# PIC32MK.net
KiCad netlist of a schematic drawn in Altium Designer
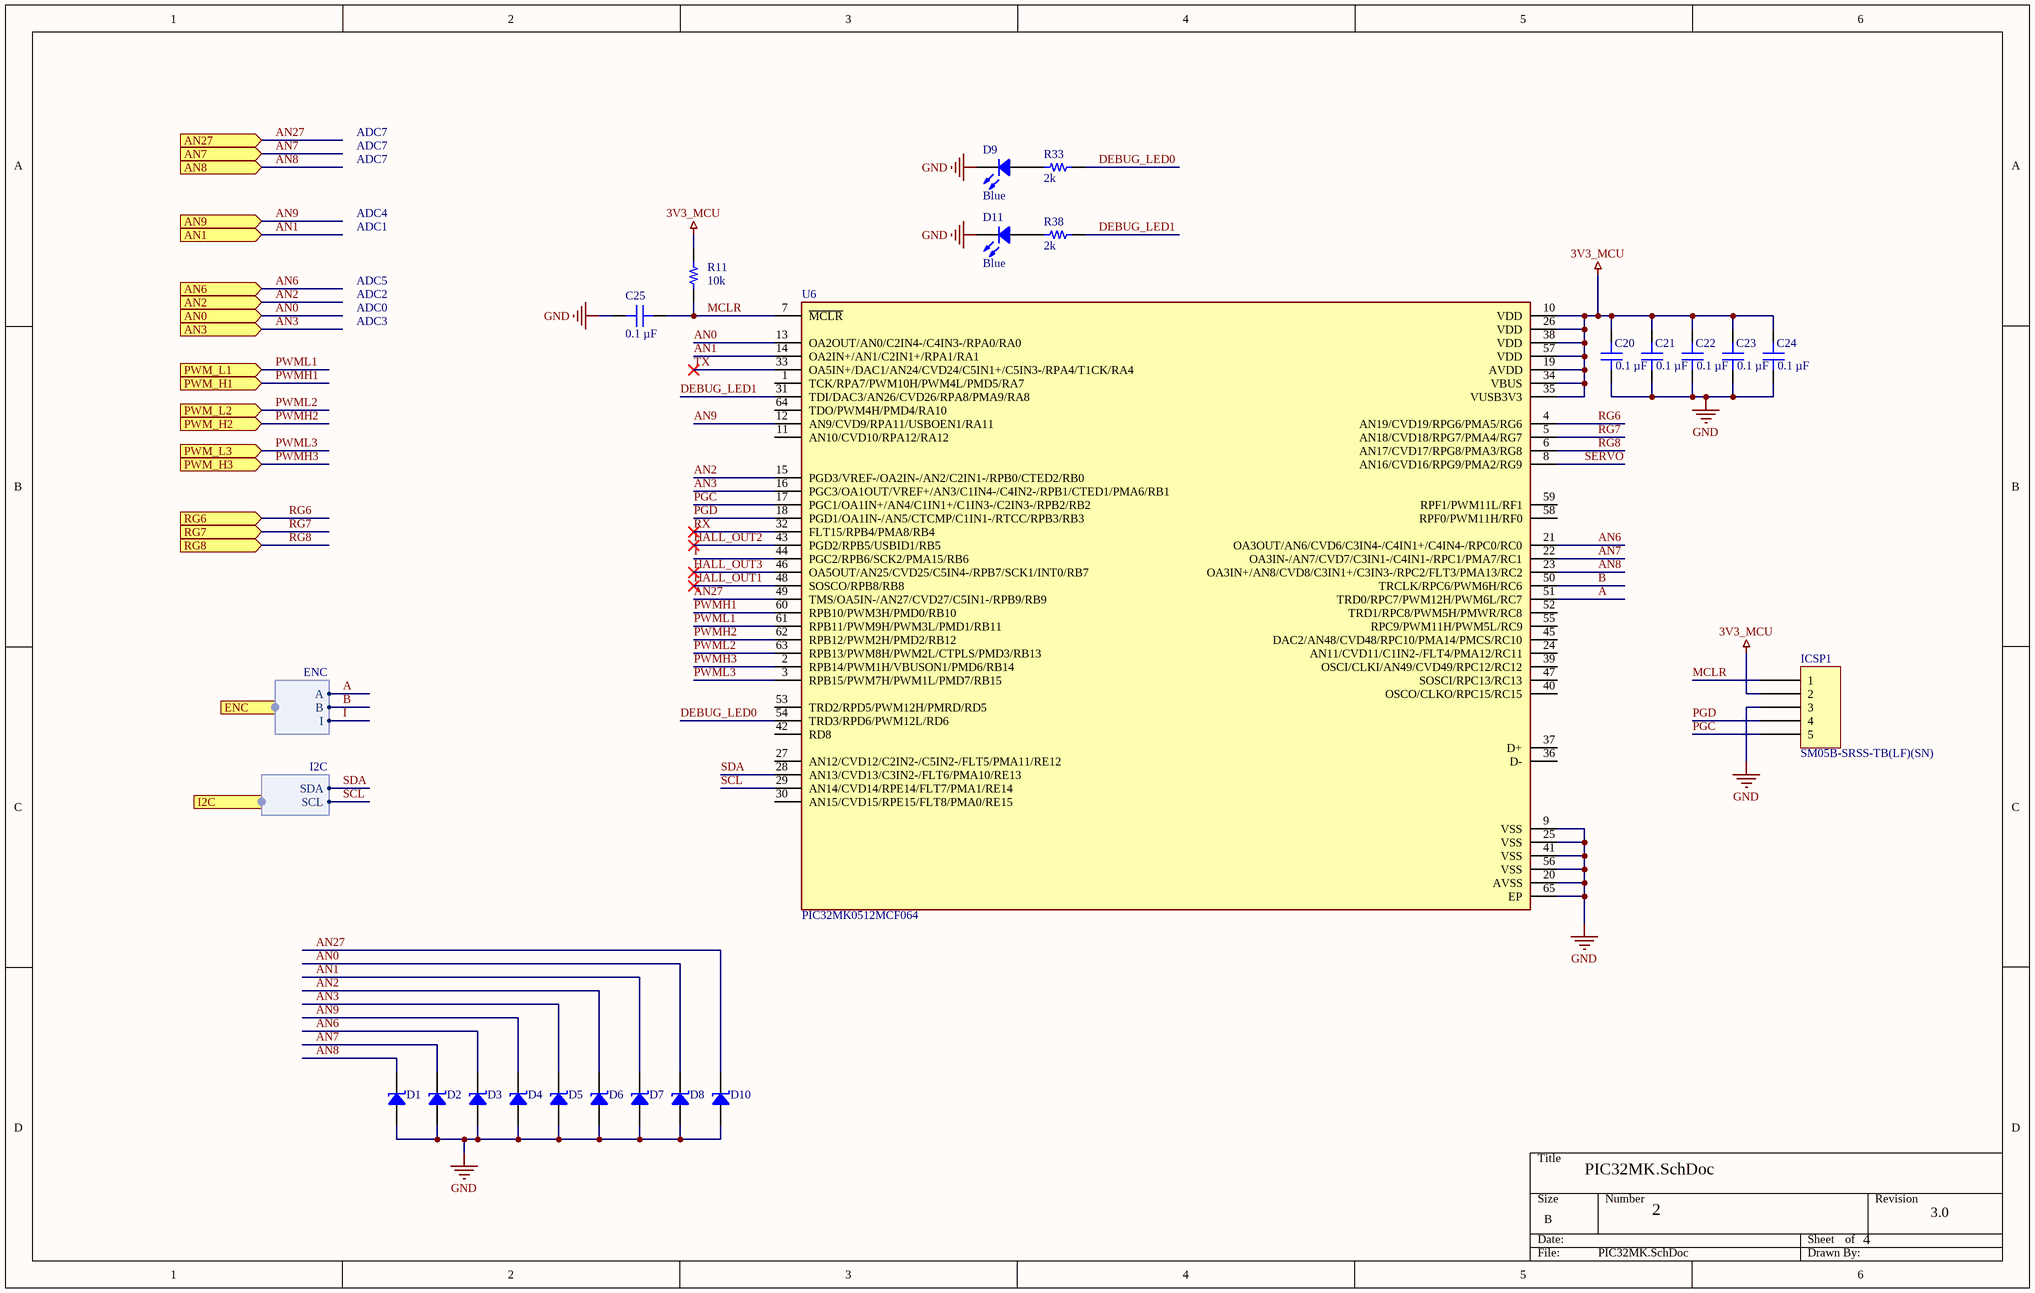
[diagram p0: PIC32MK.SchDoc]

(export (version "E")
  (design (tool "Eeschema 10.0.6"))
  (components
    (comp (ref "C20")
      (value "0.1 µF")
      (footprint "CAP 0402_1005")
      (description "CAP CER 0.1UF 16V X7R 0402")
      (fields (field (name "PART NUMBER") "C0402C104K4RACAUTO") (field (name "MANUFACTURER") "KEMET"))
      (libsource (lib "Celestial Altium Library - altium_library") (part "Capacitor"))
    )
    (comp (ref "C21")
      (value "0.1 µF")
      (footprint "CAP 0402_1005")
      (description "CAP CER 0.1UF 16V X7R 0402")
      (fields (field (name "PART NUMBER") "C0402C104K4RACAUTO") (field (name "MANUFACTURER") "KEMET"))
      (libsource (lib "Celestial Altium Library - altium_library") (part "Capacitor"))
    )
    (comp (ref "C22")
      (value "0.1 µF")
      (footprint "CAP 0402_1005")
      (description "CAP CER 0.1UF 16V X7R 0402")
      (fields (field (name "PART NUMBER") "C0402C104K4RACAUTO") (field (name "MANUFACTURER") "KEMET"))
      (libsource (lib "Celestial Altium Library - altium_library") (part "Capacitor"))
    )
    (comp (ref "C23")
      (value "0.1 µF")
      (footprint "CAP 0402_1005")
      (description "CAP CER 0.1UF 16V X7R 0402")
      (fields (field (name "PART NUMBER") "C0402C104K4RACAUTO") (field (name "MANUFACTURER") "KEMET"))
      (libsource (lib "Celestial Altium Library - altium_library") (part "Capacitor"))
    )
    (comp (ref "C24")
      (value "0.1 µF")
      (footprint "CAP 0402_1005")
      (description "CAP CER 0.1UF 16V X7R 0402")
      (fields (field (name "PART NUMBER") "C0402C104K4RACAUTO") (field (name "MANUFACTURER") "KEMET"))
      (libsource (lib "Celestial Altium Library - altium_library") (part "Capacitor"))
    )
    (comp (ref "C25")
      (value "0.1 µF")
      (footprint "CAP 0402_1005")
      (description "CAP CER 0.1UF 16V X7R 0402")
      (fields (field (name "PART NUMBER") "C0402C104K4RACAUTO") (field (name "MANUFACTURER") "KEMET"))
      (libsource (lib "Celestial Altium Library - altium_library") (part "Capacitor"))
    )
    (comp (ref "D1")
      (value "ESDLC3V3L-TP")
      (footprint "0402")
      (description "TVS DIODE 3.3V 15V DFN1006-2")
      (fields (field (name "MANUFACTURER") "Micro Commercial Co"))
      (libsource (lib "Celestial Altium Library - altium_library") (part "DIODE TVS UNI"))
    )
    (comp (ref "D2")
      (value "ESDLC3V3L-TP")
      (footprint "0402")
      (description "TVS DIODE 3.3V 15V DFN1006-2")
      (fields (field (name "MANUFACTURER") "Micro Commercial Co"))
      (libsource (lib "Celestial Altium Library - altium_library") (part "DIODE TVS UNI"))
    )
    (comp (ref "D3")
      (value "ESDLC3V3L-TP")
      (footprint "0402")
      (description "TVS DIODE 3.3V 15V DFN1006-2")
      (fields (field (name "MANUFACTURER") "Micro Commercial Co"))
      (libsource (lib "Celestial Altium Library - altium_library") (part "DIODE TVS UNI"))
    )
    (comp (ref "D4")
      (value "ESDLC3V3L-TP")
      (footprint "0402")
      (description "TVS DIODE 3.3V 15V DFN1006-2")
      (fields (field (name "MANUFACTURER") "Micro Commercial Co"))
      (libsource (lib "Celestial Altium Library - altium_library") (part "DIODE TVS UNI"))
    )
    (comp (ref "D5")
      (value "ESDLC3V3L-TP")
      (footprint "0402")
      (description "TVS DIODE 3.3V 15V DFN1006-2")
      (fields (field (name "MANUFACTURER") "Micro Commercial Co"))
      (libsource (lib "Celestial Altium Library - altium_library") (part "DIODE TVS UNI"))
    )
    (comp (ref "D6")
      (value "ESDLC3V3L-TP")
      (footprint "0402")
      (description "TVS DIODE 3.3V 15V DFN1006-2")
      (fields (field (name "MANUFACTURER") "Micro Commercial Co"))
      (libsource (lib "Celestial Altium Library - altium_library") (part "DIODE TVS UNI"))
    )
    (comp (ref "D7")
      (value "ESDLC3V3L-TP")
      (footprint "0402")
      (description "TVS DIODE 3.3V 15V DFN1006-2")
      (fields (field (name "MANUFACTURER") "Micro Commercial Co"))
      (libsource (lib "Celestial Altium Library - altium_library") (part "DIODE TVS UNI"))
    )
    (comp (ref "D8")
      (value "ESDLC3V3L-TP")
      (footprint "0402")
      (description "TVS DIODE 3.3V 15V DFN1006-2")
      (fields (field (name "MANUFACTURER") "Micro Commercial Co"))
      (libsource (lib "Celestial Altium Library - altium_library") (part "DIODE TVS UNI"))
    )
    (comp (ref "D9")
      (value "Blue")
      (footprint "LED 0603_1608 GREEN")
      (description "Blue LED")
      (fields (field (name "PART NUMBER") "XZCDGK53W-8VF") (field (name "MANUFACTURER") "SunLED"))
      (libsource (lib "Celestial Altium Library - altium_library") (part "LED"))
    )
    (comp (ref "D10")
      (value "ESDLC3V3L-TP")
      (footprint "0402")
      (description "TVS DIODE 3.3V 15V DFN1006-2")
      (fields (field (name "MANUFACTURER") "Micro Commercial Co"))
      (libsource (lib "Celestial Altium Library - altium_library") (part "DIODE TVS UNI"))
    )
    (comp (ref "D11")
      (value "Blue")
      (footprint "LED 0603_1608 GREEN")
      (description "Blue LED")
      (fields (field (name "PART NUMBER") "XZCDGK53W-8VF") (field (name "MANUFACTURER") "SunLED"))
      (libsource (lib "Celestial Altium Library - altium_library") (part "LED"))
    )
    (comp (ref "ICSP1")
      (value "SM05B-SRSS-TB(LF)(SN)")
      (footprint "JST SM05B-SRSS-TB")
      (description "CONN HEADER SMD R/A 5POS 1MM")
      (fields (field (name "MANUFACTURER") "JST Sales America Inc."))
      (libsource (lib "Celestial Altium Library - altium_library") (part "5 Pin"))
    )
    (comp (ref "R11")
      (value "10k")
      (footprint "RES 0402_1005")
      (description "RES 14.3K OHM 1% 1/10W 0402")
      (fields
        (field (name "PART NUMBER") "RK73H1ETTP1432F")
        (field (name "MANUFACTURER") "KOA Speer Electronics, Inc.")
      )
      (libsource (lib "Celestial Altium Library - altium_library") (part "Resistor"))
    )
    (comp (ref "R33")
      (value "2k")
      (footprint "RES 0402_1005")
      (description "RES 14.3K OHM 1% 1/10W 0402")
      (fields
        (field (name "PART NUMBER") "RK73H1ETTP1432F")
        (field (name "MANUFACTURER") "KOA Speer Electronics, Inc.")
      )
      (libsource (lib "Celestial Altium Library - altium_library") (part "Resistor"))
    )
    (comp (ref "R38")
      (value "2k")
      (footprint "RES 0402_1005")
      (description "RES 14.3K OHM 1% 1/10W 0402")
      (fields
        (field (name "PART NUMBER") "RK73H1ETTP1432F")
        (field (name "MANUFACTURER") "KOA Speer Electronics, Inc.")
      )
      (libsource (lib "Celestial Altium Library - altium_library") (part "Resistor"))
    )
    (comp (ref "U6")
      (value "PIC32MK0512MCF064")
      (footprint "QFN50P900X900X100-65N")
      (description "PIC32MK Microcontroller IC 32-Bit 120MHz 1MB _1M x 8_ FLASH 64-TQFP _10x10_")
      (fields
        (field (name "MP") "PIC32MK1024MCF064-I/PT")
        (field (name "DIGI-KEY_PART_NUMBER") "PIC32MK1024MCF064-I/PT-ND")
      )
      (libsource (lib "IC") (part "PIC32MK0512MCF064"))
    )
  )
  (nets
    (net (code "3") (name "/A") (class "Default")
      (node (ref "U6") (pin "51") (pinfunction "TRD0/RPC7/PWM12H/PWM6L/RC7_51") (pintype "passive"))
    )
    (net (code "4") (name "/AN0") (class "Default")
      (node (ref "D8") (pin "2") (pinfunction "2_2") (pintype "passive"))
      (node (ref "U6") (pin "13") (pinfunction "OA2OUT/AN0/C2IN4-/C4IN3-/RPA0/RA0_13") (pintype "passive"))
    )
    (net (code "5") (name "/AN1") (class "Default")
      (node (ref "D7") (pin "2") (pinfunction "2_2") (pintype "passive"))
      (node (ref "U6") (pin "14") (pinfunction "OA2IN+/AN1/C2IN1+/RPA1/RA1_14") (pintype "passive"))
    )
    (net (code "6") (name "/AN2") (class "Default")
      (node (ref "D6") (pin "2") (pinfunction "2_2") (pintype "passive"))
      (node (ref "U6") (pin "15") (pinfunction "PGD3/VREF-/OA2IN-/AN2/C2IN1-/RPB0/CTED2/RB0_15") (pintype "passive"))
    )
    (net (code "7") (name "/AN3") (class "Default")
      (node (ref "D5") (pin "2") (pinfunction "2_2") (pintype "passive"))
      (node (ref "U6") (pin "16") (pinfunction "PGC3/OA1OUT/VREF+/AN3/C1IN4-/C4IN2-/RPB1/CTED1/PMA6/RB1_16") (pintype "passive"))
    )
    (net (code "8") (name "/AN6") (class "Default")
      (node (ref "D3") (pin "2") (pinfunction "2_2") (pintype "passive"))
      (node (ref "U6") (pin "21") (pinfunction "OA3OUT/AN6/CVD6/C3IN4-/C4IN1+/C4IN4-/RPC0/RC0_21") (pintype "passive"))
    )
    (net (code "9") (name "/AN7") (class "Default")
      (node (ref "D2") (pin "2") (pinfunction "2_2") (pintype "passive"))
      (node (ref "U6") (pin "22") (pinfunction "OA3IN-/AN7/CVD7/C3IN1-/C4IN1-/RPC1/PMA7/RC1_22") (pintype "passive"))
    )
    (net (code "10") (name "/AN8") (class "Default")
      (node (ref "D1") (pin "2") (pinfunction "2_2") (pintype "passive"))
      (node (ref "U6") (pin "23") (pinfunction "OA3IN+/AN8/CVD8/C3IN1+/C3IN3-/RPC2/FLT3/PMA13/RC2_23") (pintype "passive"))
    )
    (net (code "11") (name "/AN9") (class "Default")
      (node (ref "D4") (pin "2") (pinfunction "2_2") (pintype "passive"))
      (node (ref "U6") (pin "12") (pinfunction "AN9/CVD9/RPA11/USBOEN1/RA11_12") (pintype "passive"))
    )
    (net (code "12") (name "/AN27") (class "Default")
      (node (ref "D10") (pin "2") (pinfunction "2_2") (pintype "passive"))
      (node (ref "U6") (pin "49") (pinfunction "TMS/OA5IN-/AN27/CVD27/C5IN1-/RPB9/RB9_49") (pintype "passive"))
    )
    (net (code "13") (name "/B") (class "Default")
      (node (ref "U6") (pin "50") (pinfunction "TRCLK/RPC6/PWM6H/RC6_50") (pintype "passive"))
    )
    (net (code "14") (name "/DEBUG_LED0") (class "Default")
      (node (ref "R33") (pin "1") (pinfunction "1_1") (pintype "passive"))
      (node (ref "U6") (pin "54") (pinfunction "TRD3/RPD6/PWM12L/RD6_54") (pintype "passive"))
    )
    (net (code "15") (name "/DEBUG_LED1") (class "Default")
      (node (ref "R38") (pin "1") (pinfunction "1_1") (pintype "passive"))
      (node (ref "U6") (pin "31") (pinfunction "TDI/DAC3/AN26/CVD26/RPA8/PMA9/RA8_31") (pintype "passive"))
    )
    (net (code "16") (name "/HALL_OUT1") (class "Default")
      (node (ref "U6") (pin "48") (pinfunction "SOSCO/RPB8/RB8_48") (pintype "passive+no_connect"))
    )
    (net (code "17") (name "/HALL_OUT2") (class "Default")
      (node (ref "U6") (pin "43") (pinfunction "PGD2/RPB5/USBID1/RB5_43") (pintype "passive+no_connect"))
    )
    (net (code "18") (name "/HALL_OUT3") (class "Default")
      (node (ref "U6") (pin "46") (pinfunction "OA5OUT/AN25/CVD25/C5IN4-/RPB7/SCK1/INT0/RB7_46") (pintype "passive+no_connect"))
    )
    (net (code "19") (name "/I") (class "Default")
      (node (ref "U6") (pin "44") (pinfunction "PGC2/RPB6/SCK2/PMA15/RB6_44") (pintype "passive"))
    )
    (net (code "20") (name "/MCLR") (class "Default")
      (node (ref "C25") (pin "1") (pinfunction "1_1") (pintype "passive"))
      (node (ref "ICSP1") (pin "1") (pinfunction "1_1") (pintype "passive"))
      (node (ref "R11") (pin "1") (pinfunction "1_1") (pintype "passive"))
      (node (ref "U6") (pin "7") (pinfunction "~{MCLR}_7") (pintype "passive"))
    )
    (net (code "21") (name "/PGC") (class "Default")
      (node (ref "ICSP1") (pin "5") (pinfunction "5_5") (pintype "passive"))
      (node (ref "U6") (pin "17") (pinfunction "PGC1/OA1IN+/AN4/C1IN1+/C1IN3-/C2IN3-/RPB2/RB2_17") (pintype "passive"))
    )
    (net (code "22") (name "/PGD") (class "Default")
      (node (ref "ICSP1") (pin "4") (pinfunction "4_4") (pintype "passive"))
      (node (ref "U6") (pin "18") (pinfunction "PGD1/OA1IN-/AN5/CTCMP/C1IN1-/RTCC/RPB3/RB3_18") (pintype "passive"))
    )
    (net (code "23") (name "/PWMH1") (class "Default")
      (node (ref "U6") (pin "60") (pinfunction "RPB10/PWM3H/PMD0/RB10_60") (pintype "passive"))
    )
    (net (code "24") (name "/PWMH2") (class "Default")
      (node (ref "U6") (pin "62") (pinfunction "RPB12/PWM2H/PMD2/RB12_62") (pintype "passive"))
    )
    (net (code "25") (name "/PWMH3") (class "Default")
      (node (ref "U6") (pin "2") (pinfunction "RPB14/PWM1H/VBUSON1/PMD6/RB14_2") (pintype "passive"))
    )
    (net (code "26") (name "/PWML1") (class "Default")
      (node (ref "U6") (pin "61") (pinfunction "RPB11/PWM9H/PWM3L/PMD1/RB11_61") (pintype "passive"))
    )
    (net (code "27") (name "/PWML2") (class "Default")
      (node (ref "U6") (pin "63") (pinfunction "RPB13/PWM8H/PWM2L/CTPLS/PMD3/RB13_63") (pintype "passive"))
    )
    (net (code "28") (name "/PWML3") (class "Default")
      (node (ref "U6") (pin "3") (pinfunction "RPB15/PWM7H/PWM1L/PMD7/RB15_3") (pintype "passive"))
    )
    (net (code "29") (name "/RG6") (class "Default")
      (node (ref "U6") (pin "4") (pinfunction "AN19/CVD19/RPG6/PMA5/RG6_4") (pintype "passive"))
    )
    (net (code "30") (name "/RG7") (class "Default")
      (node (ref "U6") (pin "5") (pinfunction "AN18/CVD18/RPG7/PMA4/RG7_5") (pintype "passive"))
    )
    (net (code "31") (name "/RG8") (class "Default")
      (node (ref "U6") (pin "6") (pinfunction "AN17/CVD17/RPG8/PMA3/RG8_6") (pintype "passive"))
    )
    (net (code "32") (name "/RX") (class "Default")
      (node (ref "U6") (pin "32") (pinfunction "FLT15/RPB4/PMA8/RB4_32") (pintype "passive+no_connect"))
    )
    (net (code "33") (name "/SCL") (class "Default")
      (node (ref "U6") (pin "29") (pinfunction "AN14/CVD14/RPE14/FLT7/PMA1/RE14_29") (pintype "passive"))
    )
    (net (code "34") (name "/SDA") (class "Default")
      (node (ref "U6") (pin "28") (pinfunction "AN13/CVD13/C3IN2-/FLT6/PMA10/RE13_28") (pintype "passive"))
    )
    (net (code "35") (name "/SERVO") (class "Default")
      (node (ref "U6") (pin "8") (pinfunction "AN16/CVD16/RPG9/PMA2/RG9_8") (pintype "passive"))
    )
    (net (code "36") (name "/TX") (class "Default")
      (node (ref "U6") (pin "33") (pinfunction "OA5IN+/DAC1/AN24/CVD24/C5IN1+/C5IN3-/RPA4/T1CK/RA4_33") (pintype "passive+no_connect"))
    )
    (net (code "39") (name "3V3_MCU") (class "Default")
      (node (ref "C20") (pin "2") (pinfunction "2_2") (pintype "passive"))
      (node (ref "C21") (pin "2") (pinfunction "2_2") (pintype "passive"))
      (node (ref "C22") (pin "2") (pinfunction "2_2") (pintype "passive"))
      (node (ref "C23") (pin "2") (pinfunction "2_2") (pintype "passive"))
      (node (ref "C24") (pin "2") (pinfunction "2_2") (pintype "passive"))
      (node (ref "ICSP1") (pin "2") (pinfunction "2_2") (pintype "passive"))
      (node (ref "R11") (pin "2") (pinfunction "2_2") (pintype "passive"))
      (node (ref "U6") (pin "10") (pinfunction "VDD_10") (pintype "power_in"))
      (node (ref "U6") (pin "19") (pinfunction "AVDD_19") (pintype "power_in"))
      (node (ref "U6") (pin "26") (pinfunction "VDD_26") (pintype "power_in"))
      (node (ref "U6") (pin "34") (pinfunction "VBUS_34") (pintype "power_in"))
      (node (ref "U6") (pin "35") (pinfunction "VUSB3V3_35") (pintype "passive"))
      (node (ref "U6") (pin "38") (pinfunction "VDD_38") (pintype "power_in"))
      (node (ref "U6") (pin "57") (pinfunction "VDD_57") (pintype "power_in"))
    )
    (net (code "40") (name "GND") (class "Default")
      (node (ref "C20") (pin "1") (pinfunction "1_1") (pintype "passive"))
      (node (ref "C21") (pin "1") (pinfunction "1_1") (pintype "passive"))
      (node (ref "C22") (pin "1") (pinfunction "1_1") (pintype "passive"))
      (node (ref "C23") (pin "1") (pinfunction "1_1") (pintype "passive"))
      (node (ref "C24") (pin "1") (pinfunction "1_1") (pintype "passive"))
      (node (ref "C25") (pin "2") (pinfunction "2_2") (pintype "passive"))
      (node (ref "D1") (pin "1") (pinfunction "1_1") (pintype "passive"))
      (node (ref "D10") (pin "1") (pinfunction "1_1") (pintype "passive"))
      (node (ref "D11") (pin "2") (pinfunction "2_2") (pintype "passive"))
      (node (ref "D2") (pin "1") (pinfunction "1_1") (pintype "passive"))
      (node (ref "D3") (pin "1") (pinfunction "1_1") (pintype "passive"))
      (node (ref "D4") (pin "1") (pinfunction "1_1") (pintype "passive"))
      (node (ref "D5") (pin "1") (pinfunction "1_1") (pintype "passive"))
      (node (ref "D6") (pin "1") (pinfunction "1_1") (pintype "passive"))
      (node (ref "D7") (pin "1") (pinfunction "1_1") (pintype "passive"))
      (node (ref "D8") (pin "1") (pinfunction "1_1") (pintype "passive"))
      (node (ref "D9") (pin "2") (pinfunction "2_2") (pintype "passive"))
      (node (ref "ICSP1") (pin "3") (pinfunction "3_3") (pintype "passive"))
      (node (ref "U6") (pin "20") (pinfunction "AVSS_20") (pintype "power_in"))
      (node (ref "U6") (pin "25") (pinfunction "VSS_25") (pintype "power_in"))
      (node (ref "U6") (pin "41") (pinfunction "VSS_41") (pintype "power_in"))
      (node (ref "U6") (pin "56") (pinfunction "VSS_56") (pintype "power_in"))
      (node (ref "U6") (pin "65") (pinfunction "EP_65") (pintype "power_in"))
      (node (ref "U6") (pin "9") (pinfunction "VSS_9") (pintype "power_in"))
    )
    (net (code "41") (name "Net-(D9-Pad1)") (class "Default")
      (node (ref "D9") (pin "1") (pinfunction "1_1") (pintype "passive"))
      (node (ref "R33") (pin "2") (pinfunction "2_2") (pintype "passive"))
    )
    (net (code "42") (name "Net-(D11-Pad1)") (class "Default")
      (node (ref "D11") (pin "1") (pinfunction "1_1") (pintype "passive"))
      (node (ref "R38") (pin "2") (pinfunction "2_2") (pintype "passive"))
    )
    (net (code "43") (name "unconnected-(U6-AN10{slash}CVD10{slash}RPA12{slash}RA12-Pad11)") (class "Default")
      (node (ref "U6") (pin "11") (pinfunction "AN10/CVD10/RPA12/RA12_11") (pintype "passive"))
    )
    (net (code "44") (name "unconnected-(U6-AN11{slash}CVD11{slash}C1IN2-{slash}FLT4{slash}PMA12{slash}RC11-Pad24)") (class "Default")
      (node (ref "U6") (pin "24") (pinfunction "AN11/CVD11/C1IN2-/FLT4/PMA12/RC11_24") (pintype "passive"))
    )
    (net (code "45") (name "unconnected-(U6-AN12{slash}CVD12{slash}C2IN2-{slash}C5IN2-{slash}FLT5{slash}PMA11{slash}RE12-Pad27)") (class "Default")
      (node (ref "U6") (pin "27") (pinfunction "AN12/CVD12/C2IN2-/C5IN2-/FLT5/PMA11/RE12_27") (pintype "passive"))
    )
    (net (code "46") (name "unconnected-(U6-AN15{slash}CVD15{slash}RPE15{slash}FLT8{slash}PMA0{slash}RE15-Pad30)") (class "Default")
      (node (ref "U6") (pin "30") (pinfunction "AN15/CVD15/RPE15/FLT8/PMA0/RE15_30") (pintype "passive"))
    )
    (net (code "47") (name "unconnected-(U6-D+-Pad37)") (class "Default")
      (node (ref "U6") (pin "37") (pinfunction "D+_37") (pintype "passive"))
    )
    (net (code "48") (name "unconnected-(U6-D--Pad36)") (class "Default")
      (node (ref "U6") (pin "36") (pinfunction "D-_36") (pintype "passive"))
    )
    (net (code "49") (name "unconnected-(U6-DAC2{slash}AN48{slash}CVD48{slash}RPC10{slash}PMA14{slash}PMCS{slash}RC10-Pad45)") (class "Default")
      (node (ref "U6") (pin "45") (pinfunction "DAC2/AN48/CVD48/RPC10/PMA14/PMCS/RC10_45") (pintype "passive"))
    )
    (net (code "50") (name "unconnected-(U6-OSCI{slash}CLKI{slash}AN49{slash}CVD49{slash}RPC12{slash}RC12-Pad39)") (class "Default")
      (node (ref "U6") (pin "39") (pinfunction "OSCI/CLKI/AN49/CVD49/RPC12/RC12_39") (pintype "passive"))
    )
    (net (code "51") (name "unconnected-(U6-OSCO{slash}CLKO{slash}RPC15{slash}RC15-Pad40)") (class "Default")
      (node (ref "U6") (pin "40") (pinfunction "OSCO/CLKO/RPC15/RC15_40") (pintype "passive"))
    )
    (net (code "52") (name "unconnected-(U6-RD8-Pad42)") (class "Default")
      (node (ref "U6") (pin "42") (pinfunction "RD8_42") (pintype "passive"))
    )
    (net (code "53") (name "unconnected-(U6-RPC9{slash}PWM11H{slash}PWM5L{slash}RC9-Pad55)") (class "Default")
      (node (ref "U6") (pin "55") (pinfunction "RPC9/PWM11H/PWM5L/RC9_55") (pintype "passive"))
    )
    (net (code "54") (name "unconnected-(U6-RPF0{slash}PWM11H{slash}RF0-Pad58)") (class "Default")
      (node (ref "U6") (pin "58") (pinfunction "RPF0/PWM11H/RF0_58") (pintype "passive"))
    )
    (net (code "55") (name "unconnected-(U6-RPF1{slash}PWM11L{slash}RF1-Pad59)") (class "Default")
      (node (ref "U6") (pin "59") (pinfunction "RPF1/PWM11L/RF1_59") (pintype "passive"))
    )
    (net (code "56") (name "unconnected-(U6-SOSCI{slash}RPC13{slash}RC13-Pad47)") (class "Default")
      (node (ref "U6") (pin "47") (pinfunction "SOSCI/RPC13/RC13_47") (pintype "passive"))
    )
    (net (code "57") (name "unconnected-(U6-TCK{slash}RPA7{slash}PWM10H{slash}PWM4L{slash}PMD5{slash}RA7-Pad1)") (class "Default")
      (node (ref "U6") (pin "1") (pinfunction "TCK/RPA7/PWM10H/PWM4L/PMD5/RA7_1") (pintype "passive"))
    )
    (net (code "58") (name "unconnected-(U6-TDO{slash}PWM4H{slash}PMD4{slash}RA10-Pad64)") (class "Default")
      (node (ref "U6") (pin "64") (pinfunction "TDO/PWM4H/PMD4/RA10_64") (pintype "passive"))
    )
    (net (code "59") (name "unconnected-(U6-TRD1{slash}RPC8{slash}PWM5H{slash}PMWR{slash}RC8-Pad52)") (class "Default")
      (node (ref "U6") (pin "52") (pinfunction "TRD1/RPC8/PWM5H/PMWR/RC8_52") (pintype "passive"))
    )
    (net (code "60") (name "unconnected-(U6-TRD2{slash}RPD5{slash}PWM12H{slash}PMRD{slash}RD5-Pad53)") (class "Default")
      (node (ref "U6") (pin "53") (pinfunction "TRD2/RPD5/PWM12H/PMRD/RD5_53") (pintype "passive"))
    )
  )
)
